# Sheet1.net
KiCad netlist of a schematic drawn in Altium Designer
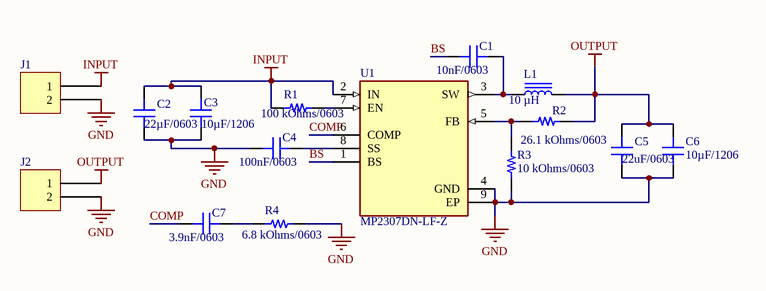
[diagram p0: Sheet1.SchDoc]

(export (version "E")
  (design (tool "Eeschema 10.0.6"))
  (components
    (comp (ref "C1")
      (value "0.1 µF")
      (footprint "CAP 0603_1608")
      (description "CAP CER 0.1UF 50V X7R 0603")
      (fields
        (field (name "PART NUMBER") "C0603C104K5RAC7411")
        (field (name "CAPACITANCE") "10nF/0603")
        (field (name "MANUFACTURER") "KEMET")
      )
      (libsource (lib "Celestial Altium Library - altium_library") (part "Capacitor"))
    )
    (comp (ref "C2")
      (value "0.1 µF")
      (footprint "CAP 0603_1608")
      (description "CAP CER 0.1UF 50V X7R 0603")
      (fields
        (field (name "PART NUMBER") "C0603C104K5RAC7411")
        (field (name "CAPACITANCE") "22µF/0603")
        (field (name "MANUFACTURER") "KEMET")
      )
      (libsource (lib "Celestial Altium Library - altium_library") (part "Capacitor"))
    )
    (comp (ref "C3")
      (value "10 µF")
      (footprint "CAP 1206_3216 - 0.8MM")
      (description "CAP CER 10UF 25V X7R 1206")
      (fields
        (field (name "PART NUMBER") "GRM31CR71E106KA12K")
        (field (name "CAPACITANCE") "10µF/1206")
        (field (name "MANUFACTURER") "Murata Electronics")
      )
      (libsource (lib "Celestial Altium Library - altium_library") (part "Capacitor"))
    )
    (comp (ref "C4")
      (value "0.1 µF")
      (footprint "CAP 0603_1608")
      (description "CAP CER 0.1UF 50V X7R 0603")
      (fields
        (field (name "PART NUMBER") "C0603C104K5RAC7411")
        (field (name "CAPACITANCE") "100nF/0603")
        (field (name "MANUFACTURER") "KEMET")
      )
      (libsource (lib "Celestial Altium Library - altium_library") (part "Capacitor"))
    )
    (comp (ref "C5")
      (value "0.1 µF")
      (footprint "CAP 0603_1608")
      (description "CAP CER 0.1UF 50V X7R 0603")
      (fields
        (field (name "PART NUMBER") "C0603C104K5RAC7411")
        (field (name "CAPACITANCE") "22uF/0603")
        (field (name "MANUFACTURER") "KEMET")
      )
      (libsource (lib "Celestial Altium Library - altium_library") (part "Capacitor"))
    )
    (comp (ref "C6")
      (value "10 µF")
      (footprint "CAP 1206_3216 - 0.8MM")
      (description "CAP CER 10UF 25V X7R 1206")
      (fields
        (field (name "PART NUMBER") "GRM31CR71E106KA12K")
        (field (name "CAPACITANCE") "10µF/1206")
        (field (name "MANUFACTURER") "Murata Electronics")
      )
      (libsource (lib "Celestial Altium Library - altium_library") (part "Capacitor"))
    )
    (comp (ref "C7")
      (value "0.1 µF")
      (footprint "CAP 0603_1608")
      (description "CAP CER 0.1UF 50V X7R 0603")
      (fields
        (field (name "PART NUMBER") "C0603C104K5RAC7411")
        (field (name "CAPACITANCE") "3.9nF/0603")
        (field (name "MANUFACTURER") "KEMET")
      )
      (libsource (lib "Celestial Altium Library - altium_library") (part "Capacitor"))
    )
    (comp (ref "J1")
      (value "B2B-XH-A(LF)(SN)")
      (footprint "JST XH B2B-XH-A")
      (description "CONN HEADER VERT 2POS 2.5MM")
      (fields (field (name "MANUFACTURER") "JST Sales America Inc."))
      (libsource (lib "Celestial Altium Library - altium_library") (part "2 Pin"))
    )
    (comp (ref "J2")
      (value "B2B-XH-A(LF)(SN)")
      (footprint "JST XH B2B-XH-A")
      (description "CONN HEADER VERT 2POS 2.5MM")
      (fields (field (name "MANUFACTURER") "JST Sales America Inc."))
      (libsource (lib "Celestial Altium Library - altium_library") (part "2 Pin"))
    )
    (comp (ref "L1")
      (value "10 µH")
      (footprint "BOURNS SRP5030T")
      (description "FIXED IND 10UH 2.75A 128MOHM SMD")
      (fields (field (name "PART NUMBER") "SRP5030T-100M") (field (name "MANUFACTURER") "Bourns Inc."))
      (libsource (lib "Celestial Altium Library - altium_library") (part "Inductor"))
    )
    (comp (ref "R1")
      (value "100 kOhms/0603")
      (footprint "RES 0603_1608")
      (description "RES 10K OHM 0.1% 1/16W 0603")
      (fields
        (field (name "PART NUMBER") "RNCS0603BKE10K0")
        (field (name "MANUFACTURER") "Stackpole Electronics Inc")
      )
      (libsource (lib "Celestial Altium Library - altium_library") (part "Resistor"))
    )
    (comp (ref "R2")
      (value "26.1 kOhms/0603")
      (footprint "RES 0603_1608")
      (description "RES 10K OHM 0.1% 1/16W 0603")
      (fields
        (field (name "PART NUMBER") "RNCS0603BKE10K0")
        (field (name "MANUFACTURER") "Stackpole Electronics Inc")
      )
      (libsource (lib "Celestial Altium Library - altium_library") (part "Resistor"))
    )
    (comp (ref "R3")
      (value "10 kOhms/0603")
      (footprint "RES 0603_1608")
      (description "RES 10K OHM 0.1% 1/16W 0603")
      (fields
        (field (name "PART NUMBER") "RNCS0603BKE10K0")
        (field (name "MANUFACTURER") "Stackpole Electronics Inc")
      )
      (libsource (lib "Celestial Altium Library - altium_library") (part "Resistor"))
    )
    (comp (ref "R4")
      (value "6.8 kOhms/0603")
      (footprint "RES 0603_1608")
      (description "RES 10K OHM 0.1% 1/16W 0603")
      (fields
        (field (name "PART NUMBER") "RNCS0603BKE10K0")
        (field (name "MANUFACTURER") "Stackpole Electronics Inc")
      )
      (libsource (lib "Celestial Altium Library - altium_library") (part "Resistor"))
    )
    (comp (ref "U1")
      (value "MP2307DN-LF-Z")
      (footprint "SOIC127P600X170-9N")
      (fields (field (name "MF") "Monolithic Power"))
      (libsource (lib "MP2307DN-LF-Z") (part "MP2307DN-LF-Z"))
    )
  )
  (nets
    (net (code "1") (name "/BS") (class "Default")
      (node (ref "C1") (pin "1") (pinfunction "1_1") (pintype "passive"))
      (node (ref "U1") (pin "1") (pinfunction "BS_1") (pintype "passive"))
    )
    (net (code "2") (name "/COMP") (class "Default")
      (node (ref "C7") (pin "1") (pinfunction "1_1") (pintype "passive"))
      (node (ref "U1") (pin "6") (pinfunction "COMP_6") (pintype "passive"))
    )
    (net (code "3") (name "GND") (class "Default")
      (node (ref "C2") (pin "1") (pinfunction "1_1") (pintype "passive"))
      (node (ref "C3") (pin "1") (pinfunction "1_1") (pintype "passive"))
      (node (ref "C4") (pin "1") (pinfunction "1_1") (pintype "passive"))
      (node (ref "C5") (pin "2") (pinfunction "2_2") (pintype "passive"))
      (node (ref "C6") (pin "1") (pinfunction "1_1") (pintype "passive"))
      (node (ref "J1") (pin "2") (pinfunction "2_2") (pintype "passive"))
      (node (ref "J2") (pin "2") (pinfunction "2_2") (pintype "passive"))
      (node (ref "R3") (pin "1") (pinfunction "1_1") (pintype "passive"))
      (node (ref "R4") (pin "1") (pinfunction "1_1") (pintype "passive"))
      (node (ref "U1") (pin "4") (pinfunction "GND_4") (pintype "power_in"))
      (node (ref "U1") (pin "9") (pinfunction "EP_9") (pintype "power_in"))
    )
    (net (code "4") (name "INPUT") (class "Default")
      (node (ref "C2") (pin "2") (pinfunction "2_2") (pintype "passive"))
      (node (ref "C3") (pin "2") (pinfunction "2_2") (pintype "passive"))
      (node (ref "J1") (pin "1") (pinfunction "1_1") (pintype "passive"))
      (node (ref "R1") (pin "1") (pinfunction "1_1") (pintype "passive"))
      (node (ref "U1") (pin "2") (pinfunction "IN_2") (pintype "input"))
    )
    (net (code "5") (name "Net-(C7-Pad2)") (class "Default")
      (node (ref "C7") (pin "2") (pinfunction "2_2") (pintype "passive"))
      (node (ref "R4") (pin "2") (pinfunction "2_2") (pintype "passive"))
    )
    (net (code "6") (name "Net-(U1-EN)") (class "Default")
      (node (ref "R1") (pin "2") (pinfunction "2_2") (pintype "passive"))
      (node (ref "U1") (pin "7") (pinfunction "EN_7") (pintype "input"))
    )
    (net (code "7") (name "Net-(U1-FB)") (class "Default")
      (node (ref "R2") (pin "1") (pinfunction "1_1") (pintype "passive"))
      (node (ref "R3") (pin "2") (pinfunction "2_2") (pintype "passive"))
      (node (ref "U1") (pin "5") (pinfunction "FB_5") (pintype "input"))
    )
    (net (code "8") (name "Net-(U1-SS)") (class "Default")
      (node (ref "C4") (pin "2") (pinfunction "2_2") (pintype "passive"))
      (node (ref "U1") (pin "8") (pinfunction "SS_8") (pintype "passive"))
    )
    (net (code "9") (name "Net-(U1-SW)") (class "Default")
      (node (ref "C1") (pin "2") (pinfunction "2_2") (pintype "passive"))
      (node (ref "L1") (pin "1") (pinfunction "1_1") (pintype "passive"))
      (node (ref "U1") (pin "3") (pinfunction "SW_3") (pintype "output"))
    )
    (net (code "10") (name "OUTPUT") (class "Default")
      (node (ref "C5") (pin "1") (pinfunction "1_1") (pintype "passive"))
      (node (ref "C6") (pin "2") (pinfunction "2_2") (pintype "passive"))
      (node (ref "J2") (pin "1") (pinfunction "1_1") (pintype "passive"))
      (node (ref "L1") (pin "2") (pinfunction "2_2") (pintype "passive"))
      (node (ref "R2") (pin "2") (pinfunction "2_2") (pintype "passive"))
    )
  )
)
